# simple-transmitter-bc547.net
KiCad netlist of a schematic drawn in EAGLE
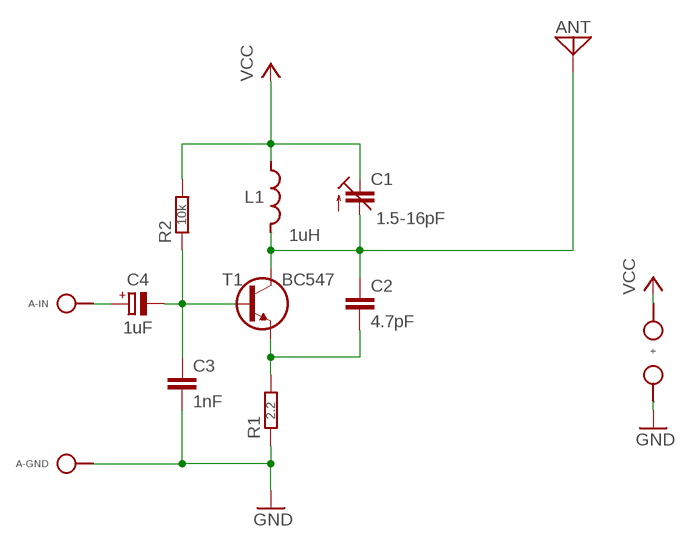
[diagram p0: schematic, sheet 1]

(export (version "E")
  (design (tool "Eeschema 10.0.6"))
  (components
    (comp (ref "+")
      (value "SPAD")
      (footprint "eagle-import:SPAD")
      (libsource (lib "eagle-import") (part "SPAD"))
    )
    (comp (ref "A-GND")
      (value "SPAD")
      (footprint "eagle-import:SPAD")
      (libsource (lib "eagle-import") (part "SPAD"))
    )
    (comp (ref "A-IN")
      (value "SPAD")
      (footprint "eagle-import:SPAD")
      (libsource (lib "eagle-import") (part "SPAD"))
    )
    (comp (ref "ANT")
      (value "ANT")
      (footprint "eagle-import:SPAD")
      (libsource (lib "eagle-import") (part "ANT"))
    )
    (comp (ref "C1")
      (value "1.5-16pF")
      (footprint "eagle-import:TRIM808-45")
      (libsource (lib "eagle-import") (part "C-TR-PH20127-45-2P23"))
    )
    (comp (ref "C2")
      (value "4.7pF")
      (footprint "eagle-import:C050-020X036-M")
      (libsource (lib "eagle-import") (part "C050-020X036-M"))
    )
    (comp (ref "C3")
      (value "1nF")
      (footprint "eagle-import:C050-020X036")
      (libsource (lib "eagle-import") (part "C050-020X036"))
    )
    (comp (ref "C4")
      (value "1uF")
      (footprint "eagle-import:E2,5-3")
      (libsource (lib "eagle-import") (part "CPOLE2,5-3"))
    )
    (comp (ref "L1")
      (value "1uH")
      (footprint "eagle-import:L-04_7")
      (libsource (lib "eagle-import") (part "L-SHORT04/7"))
    )
    (comp (ref "R1")
      (value "2.2")
      (footprint "eagle-import:0202V")
      (libsource (lib "eagle-import") (part "R0202V"))
    )
    (comp (ref "R2")
      (value "10k")
      (footprint "eagle-import:0202_5-V")
      (libsource (lib "eagle-import") (part "R0202/5-V"))
    )
    (comp (ref "T1")
      (value "BC547")
      (footprint "eagle-import:TO92-CBE")
      (libsource (lib "eagle-import") (part "BC547CBE"))
    )
    (comp (ref "̶̶")
      (value "SPAD")
      (footprint "eagle-import:SPAD")
      (libsource (lib "eagle-import") (part "SPAD"))
    )
  )
  (nets
    (net (code "1") (name "GND") (class "Default")
      (node (ref "A-GND") (pin "1") (pinfunction "P$1_1") (pintype "bidirectional"))
      (node (ref "C3") (pin "2") (pinfunction "2_2") (pintype "passive"))
      (node (ref "R1") (pin "1") (pinfunction "1_1") (pintype "passive"))
      (node (ref "̶̶") (pin "1") (pinfunction "P$1_1") (pintype "bidirectional"))
    )
    (net (code "2") (name "Net-(A-IN-P$1)") (class "Default")
      (node (ref "A-IN") (pin "1") (pinfunction "P$1_1") (pintype "bidirectional"))
      (node (ref "C4") (pin "+") (pinfunction "+_+") (pintype "passive"))
    )
    (net (code "3") (name "Net-(C1-E)") (class "Default")
      (node (ref "ANT") (pin "1") (pinfunction "1_1") (pintype "output"))
      (node (ref "C1") (pin "2") (pinfunction "E_2") (pintype "passive"))
      (node (ref "C2") (pin "1") (pinfunction "1_1") (pintype "passive"))
      (node (ref "L1") (pin "2") (pinfunction "2_2") (pintype "passive"))
      (node (ref "T1") (pin "C") (pinfunction "C_C") (pintype "passive"))
    )
    (net (code "4") (name "Net-(C2-Pad2)") (class "Default")
      (node (ref "C2") (pin "2") (pinfunction "2_2") (pintype "passive"))
      (node (ref "R1") (pin "2") (pinfunction "2_2") (pintype "passive"))
      (node (ref "T1") (pin "E") (pinfunction "E_E") (pintype "passive"))
    )
    (net (code "5") (name "Net-(C3-Pad1)") (class "Default")
      (node (ref "C3") (pin "1") (pinfunction "1_1") (pintype "passive"))
      (node (ref "C4") (pin "-") (pinfunction "-_-") (pintype "passive"))
      (node (ref "R2") (pin "1") (pinfunction "1_1") (pintype "passive"))
      (node (ref "T1") (pin "B") (pinfunction "B_B") (pintype "passive"))
    )
    (net (code "6") (name "VCC") (class "Default")
      (node (ref "+") (pin "1") (pinfunction "P$1_1") (pintype "bidirectional"))
      (node (ref "C1") (pin "3") (pinfunction "A_3") (pintype "passive"))
      (node (ref "L1") (pin "1") (pinfunction "1_1") (pintype "passive"))
      (node (ref "R2") (pin "2") (pinfunction "2_2") (pintype "passive"))
    )
  )
)
